# power-monitor.net
KiCad netlist of a schematic drawn in EAGLE
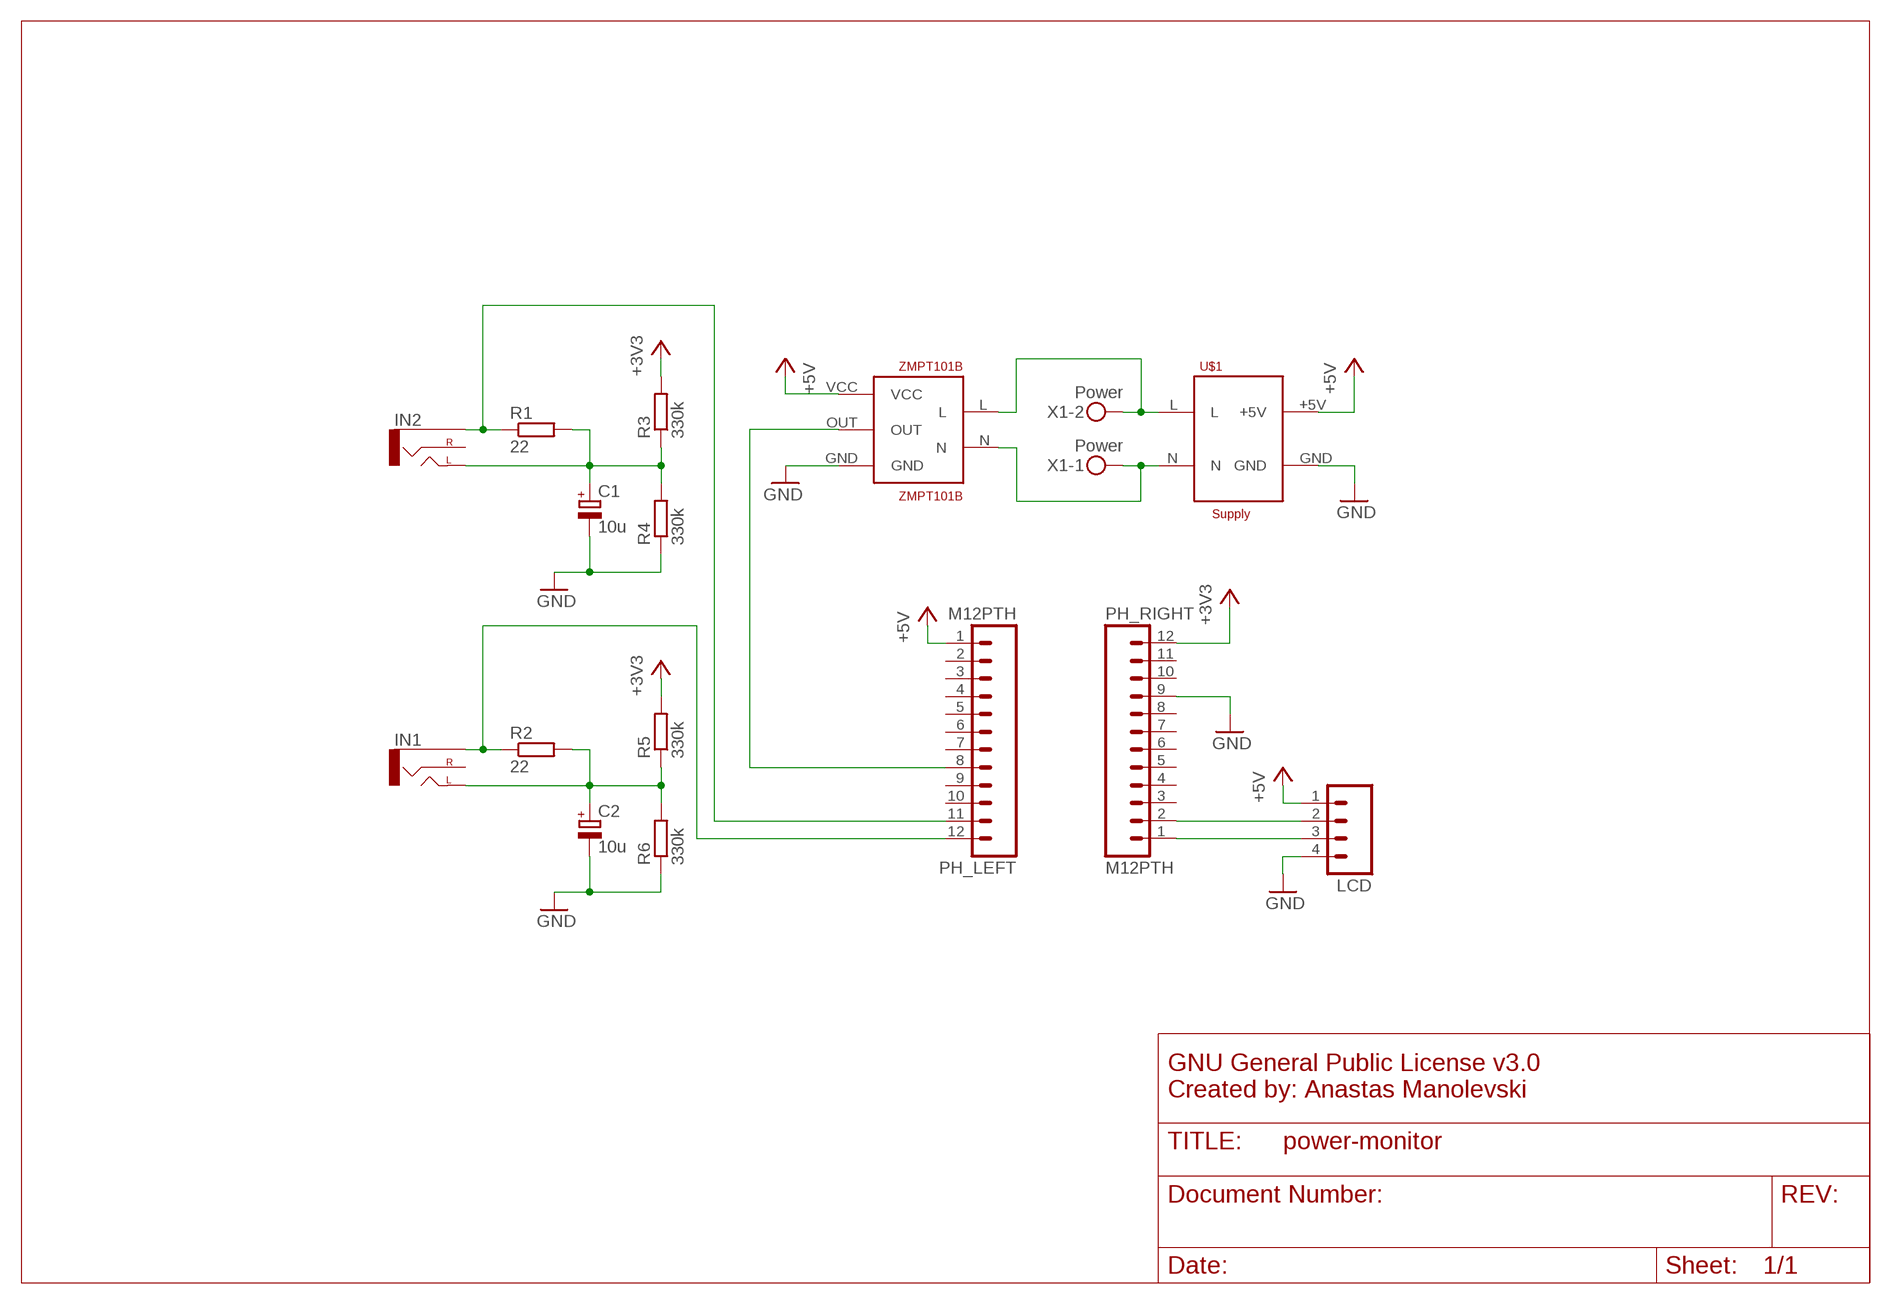
[diagram p0: schematic, sheet 1]

(export (version "E")
  (design (tool "Eeschema 10.0.6"))
  (components
    (comp (ref "C1")
      (value "10u")
      (footprint "eagle-import:E2,5-5")
      (libsource (lib "eagle-import") (part "CPOL-EUE2.5-5"))
    )
    (comp (ref "C2")
      (value "10u")
      (footprint "eagle-import:E2,5-5")
      (libsource (lib "eagle-import") (part "CPOL-EUE2.5-5"))
    )
    (comp (ref "IN1")
      (value "AUDIO-JACKPTH")
      (footprint "eagle-import:AUDIO-JACK")
      (libsource (lib "eagle-import") (part "AUDIO-JACKPTH"))
    )
    (comp (ref "IN2")
      (value "AUDIO-JACKPTH")
      (footprint "eagle-import:AUDIO-JACK")
      (libsource (lib "eagle-import") (part "AUDIO-JACKPTH"))
    )
    (comp (ref "LCD")
      (value "M04PTH")
      (footprint "eagle-import:1X04")
      (libsource (lib "eagle-import") (part "M04PTH"))
    )
    (comp (ref "PH_LEFT")
      (value "M12PTH")
      (footprint "eagle-import:1X12-SMALL-PADS")
      (libsource (lib "eagle-import") (part "M12PTH"))
    )
    (comp (ref "PH_RIGHT")
      (value "M12PTH")
      (footprint "eagle-import:1X12-SMALL-PADS")
      (libsource (lib "eagle-import") (part "M12PTH"))
    )
    (comp (ref "R1")
      (value "22")
      (footprint "eagle-import:0204_7")
      (libsource (lib "eagle-import") (part "R-EU_0204/7"))
    )
    (comp (ref "R2")
      (value "22")
      (footprint "eagle-import:0204_7")
      (libsource (lib "eagle-import") (part "R-EU_0204/7"))
    )
    (comp (ref "R3")
      (value "330k")
      (footprint "eagle-import:0204_7")
      (libsource (lib "eagle-import") (part "R-EU_0204/7"))
    )
    (comp (ref "R4")
      (value "330k")
      (footprint "eagle-import:0204_7")
      (libsource (lib "eagle-import") (part "R-EU_0204/7"))
    )
    (comp (ref "R5")
      (value "330k")
      (footprint "eagle-import:0204_7")
      (libsource (lib "eagle-import") (part "R-EU_0204/7"))
    )
    (comp (ref "R6")
      (value "330k")
      (footprint "eagle-import:0204_7")
      (libsource (lib "eagle-import") (part "R-EU_0204/7"))
    )
    (comp (ref "U$1")
      (value "Supply")
      (footprint "eagle-import:PWR-SUPP")
      (libsource (lib "eagle-import") (part "PWR-SUPP"))
    )
    (comp (ref "X1")
      (value "Power")
      (footprint "eagle-import:MKDSN1,5_2-5,08")
      (libsource (lib "eagle-import") (part "MKDSN1,5/2-5,08"))
    )
    (comp (ref "ZMPT101B")
      (value "ZMPT101B")
      (footprint "eagle-import:ZMPT101B")
      (libsource (lib "eagle-import") (part "ZMPT101B"))
    )
  )
  (nets
    (net (code "1") (name "+3V3") (class "Default")
      (node (ref "PH_RIGHT") (pin "12") (pinfunction "12_12") (pintype "passive"))
      (node (ref "R3") (pin "2") (pinfunction "2_2") (pintype "passive"))
      (node (ref "R5") (pin "2") (pinfunction "2_2") (pintype "passive"))
    )
    (net (code "2") (name "+5V") (class "Default")
      (node (ref "LCD") (pin "1") (pinfunction "1_1") (pintype "passive"))
      (node (ref "PH_LEFT") (pin "1") (pinfunction "1_1") (pintype "passive"))
      (node (ref "U$1") (pin "+5V") (pinfunction "+5V_+5V") (pintype "bidirectional"))
      (node (ref "ZMPT101B") (pin "VCC") (pinfunction "VCC_VCC") (pintype "bidirectional"))
    )
    (net (code "3") (name "GND") (class "Default")
      (node (ref "C1") (pin "-") (pinfunction "-_-") (pintype "passive"))
      (node (ref "C2") (pin "-") (pinfunction "-_-") (pintype "passive"))
      (node (ref "LCD") (pin "4") (pinfunction "4_4") (pintype "passive"))
      (node (ref "PH_RIGHT") (pin "9") (pinfunction "9_9") (pintype "passive"))
      (node (ref "R4") (pin "1") (pinfunction "1_1") (pintype "passive"))
      (node (ref "R6") (pin "1") (pinfunction "1_1") (pintype "passive"))
      (node (ref "U$1") (pin "GND") (pinfunction "GND_GND") (pintype "bidirectional"))
      (node (ref "ZMPT101B") (pin "GND") (pinfunction "GND_GND") (pintype "bidirectional"))
    )
    (net (code "4") (name "Net-(IN1-LEFT)") (class "Default")
      (node (ref "C2") (pin "+") (pinfunction "+_+") (pintype "passive"))
      (node (ref "IN1") (pin "TIP") (pinfunction "LEFT_TIP") (pintype "bidirectional"))
      (node (ref "R2") (pin "2") (pinfunction "2_2") (pintype "passive"))
      (node (ref "R5") (pin "1") (pinfunction "1_1") (pintype "passive"))
      (node (ref "R6") (pin "2") (pinfunction "2_2") (pintype "passive"))
    )
    (net (code "5") (name "Net-(IN1-PadSLEEVE)") (class "Default")
      (node (ref "IN1") (pin "SLEEVE") (pinfunction "SLEEVE_SLEEVE") (pintype "bidirectional"))
      (node (ref "PH_LEFT") (pin "12") (pinfunction "12_12") (pintype "passive"))
      (node (ref "R2") (pin "1") (pinfunction "1_1") (pintype "passive"))
    )
    (net (code "6") (name "Net-(IN2-LEFT)") (class "Default")
      (node (ref "C1") (pin "+") (pinfunction "+_+") (pintype "passive"))
      (node (ref "IN2") (pin "TIP") (pinfunction "LEFT_TIP") (pintype "bidirectional"))
      (node (ref "R1") (pin "2") (pinfunction "2_2") (pintype "passive"))
      (node (ref "R3") (pin "1") (pinfunction "1_1") (pintype "passive"))
      (node (ref "R4") (pin "2") (pinfunction "2_2") (pintype "passive"))
    )
    (net (code "7") (name "Net-(IN2-PadSLEEVE)") (class "Default")
      (node (ref "IN2") (pin "SLEEVE") (pinfunction "SLEEVE_SLEEVE") (pintype "bidirectional"))
      (node (ref "PH_LEFT") (pin "11") (pinfunction "11_11") (pintype "passive"))
      (node (ref "R1") (pin "1") (pinfunction "1_1") (pintype "passive"))
    )
    (net (code "8") (name "Net-(LCD-Pad2)") (class "Default")
      (node (ref "LCD") (pin "2") (pinfunction "2_2") (pintype "passive"))
      (node (ref "PH_RIGHT") (pin "2") (pinfunction "2_2") (pintype "passive"))
    )
    (net (code "9") (name "Net-(LCD-Pad3)") (class "Default")
      (node (ref "LCD") (pin "3") (pinfunction "3_3") (pintype "passive"))
      (node (ref "PH_RIGHT") (pin "1") (pinfunction "1_1") (pintype "passive"))
    )
    (net (code "10") (name "Net-(PH_LEFT-Pad8)") (class "Default")
      (node (ref "PH_LEFT") (pin "8") (pinfunction "8_8") (pintype "passive"))
      (node (ref "ZMPT101B") (pin "OUT") (pinfunction "OUT_OUT") (pintype "bidirectional"))
    )
    (net (code "11") (name "Net-(X1A-KL)") (class "Default")
      (node (ref "U$1") (pin "N") (pinfunction "N_N") (pintype "bidirectional"))
      (node (ref "X1") (pin "1") (pinfunction "KL_1") (pintype "passive"))
      (node (ref "ZMPT101B") (pin "N") (pinfunction "N_N") (pintype "bidirectional"))
    )
    (net (code "12") (name "Net-(X1B-KL)") (class "Default")
      (node (ref "U$1") (pin "L") (pinfunction "L_L") (pintype "bidirectional"))
      (node (ref "X1") (pin "2") (pinfunction "KL_2") (pintype "passive"))
      (node (ref "ZMPT101B") (pin "L") (pinfunction "L_L") (pintype "bidirectional"))
    )
    (net (code "13") (name "unconnected-(IN1-RIGHT-PadRING)") (class "Default")
      (node (ref "IN1") (pin "RING") (pinfunction "RIGHT_RING") (pintype "bidirectional"))
    )
    (net (code "14") (name "unconnected-(IN2-RIGHT-PadRING)") (class "Default")
      (node (ref "IN2") (pin "RING") (pinfunction "RIGHT_RING") (pintype "bidirectional"))
    )
    (net (code "15") (name "unconnected-(PH_LEFT-Pad2)") (class "Default")
      (node (ref "PH_LEFT") (pin "2") (pinfunction "2_2") (pintype "passive"))
    )
    (net (code "16") (name "unconnected-(PH_LEFT-Pad3)") (class "Default")
      (node (ref "PH_LEFT") (pin "3") (pinfunction "3_3") (pintype "passive"))
    )
    (net (code "17") (name "unconnected-(PH_LEFT-Pad4)") (class "Default")
      (node (ref "PH_LEFT") (pin "4") (pinfunction "4_4") (pintype "passive"))
    )
    (net (code "18") (name "unconnected-(PH_LEFT-Pad5)") (class "Default")
      (node (ref "PH_LEFT") (pin "5") (pinfunction "5_5") (pintype "passive"))
    )
    (net (code "19") (name "unconnected-(PH_LEFT-Pad6)") (class "Default")
      (node (ref "PH_LEFT") (pin "6") (pinfunction "6_6") (pintype "passive"))
    )
    (net (code "20") (name "unconnected-(PH_LEFT-Pad7)") (class "Default")
      (node (ref "PH_LEFT") (pin "7") (pinfunction "7_7") (pintype "passive"))
    )
    (net (code "21") (name "unconnected-(PH_LEFT-Pad9)") (class "Default")
      (node (ref "PH_LEFT") (pin "9") (pinfunction "9_9") (pintype "passive"))
    )
    (net (code "22") (name "unconnected-(PH_LEFT-Pad10)") (class "Default")
      (node (ref "PH_LEFT") (pin "10") (pinfunction "10_10") (pintype "passive"))
    )
    (net (code "23") (name "unconnected-(PH_RIGHT-Pad3)") (class "Default")
      (node (ref "PH_RIGHT") (pin "3") (pinfunction "3_3") (pintype "passive"))
    )
    (net (code "24") (name "unconnected-(PH_RIGHT-Pad4)") (class "Default")
      (node (ref "PH_RIGHT") (pin "4") (pinfunction "4_4") (pintype "passive"))
    )
    (net (code "25") (name "unconnected-(PH_RIGHT-Pad5)") (class "Default")
      (node (ref "PH_RIGHT") (pin "5") (pinfunction "5_5") (pintype "passive"))
    )
    (net (code "26") (name "unconnected-(PH_RIGHT-Pad6)") (class "Default")
      (node (ref "PH_RIGHT") (pin "6") (pinfunction "6_6") (pintype "passive"))
    )
    (net (code "27") (name "unconnected-(PH_RIGHT-Pad7)") (class "Default")
      (node (ref "PH_RIGHT") (pin "7") (pinfunction "7_7") (pintype "passive"))
    )
    (net (code "28") (name "unconnected-(PH_RIGHT-Pad8)") (class "Default")
      (node (ref "PH_RIGHT") (pin "8") (pinfunction "8_8") (pintype "passive"))
    )
    (net (code "29") (name "unconnected-(PH_RIGHT-Pad10)") (class "Default")
      (node (ref "PH_RIGHT") (pin "10") (pinfunction "10_10") (pintype "passive"))
    )
    (net (code "30") (name "unconnected-(PH_RIGHT-Pad11)") (class "Default")
      (node (ref "PH_RIGHT") (pin "11") (pinfunction "11_11") (pintype "passive"))
    )
  )
)
